# ATMEGA128.net
KiCad netlist of a schematic drawn in Altium Designer
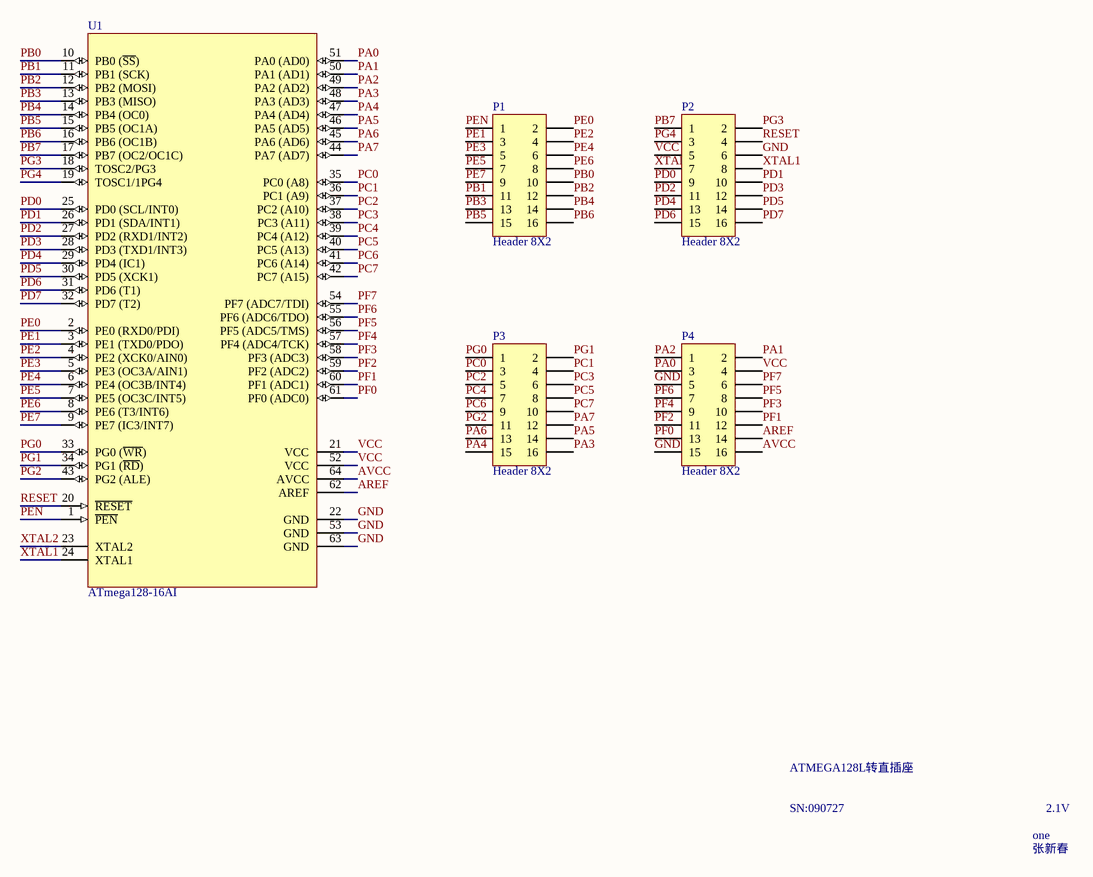
[diagram p0: ATMEGA128转换座.SchDoc]

(export (version "E")
  (design (tool "Eeschema 10.0.6"))
  (components
    (comp (ref "P1")
      (value "Header 8X2")
      (footprint "HDR2X8")
      (description "Header, 8-Pin, Dual row")
      (fields (field (name "PUBLISHER") "Altium Limited"))
      (libsource (lib "Miscellaneous Connectors") (part "Header 8X2"))
    )
    (comp (ref "P2")
      (value "Header 8X2")
      (footprint "HDR2X8")
      (description "Header, 8-Pin, Dual row")
      (fields (field (name "PUBLISHER") "Altium Limited"))
      (libsource (lib "Miscellaneous Connectors") (part "Header 8X2"))
    )
    (comp (ref "P3")
      (value "Header 8X2")
      (footprint "HDR2X8")
      (description "Header, 8-Pin, Dual row")
      (fields (field (name "PUBLISHER") "Altium Limited"))
      (libsource (lib "Miscellaneous Connectors") (part "Header 8X2"))
    )
    (comp (ref "P4")
      (value "Header 8X2")
      (footprint "HDR2X8")
      (description "Header, 8-Pin, Dual row")
      (fields (field (name "PUBLISHER") "Altium Limited"))
      (libsource (lib "Miscellaneous Connectors") (part "Header 8X2"))
    )
    (comp (ref "U1")
      (value "ATmega128-16AI")
      (footprint "64A")
      (description "8-Bit AVR Microcontroller with 128K Bytes of In-System Programmable Flash Memory")
      (fields (field (name "PUBLISHER") "Altium Limited"))
      (libsource (lib "Atmel Microcontroller 8-Bit AVR") (part "ATmega128-16AI"))
    )
  )
  (nets
    (net (code "1") (name "/AREF") (class "Default")
      (node (ref "P4") (pin "14") (pinfunction "14_14") (pintype "passive"))
      (node (ref "U1") (pin "62") (pinfunction "AREF_62") (pintype "passive"))
    )
    (net (code "2") (name "/AVCC") (class "Default")
      (node (ref "P4") (pin "16") (pinfunction "16_16") (pintype "passive"))
      (node (ref "U1") (pin "64") (pinfunction "AVCC_64") (pintype "power_in"))
    )
    (net (code "3") (name "/GND") (class "Default")
      (node (ref "P2") (pin "6") (pinfunction "6_6") (pintype "passive"))
      (node (ref "P4") (pin "15") (pinfunction "15_15") (pintype "passive"))
      (node (ref "P4") (pin "5") (pinfunction "5_5") (pintype "passive"))
      (node (ref "U1") (pin "22") (pinfunction "GND_22") (pintype "power_in"))
      (node (ref "U1") (pin "53") (pinfunction "GND_53") (pintype "power_in"))
      (node (ref "U1") (pin "63") (pinfunction "GND_63") (pintype "power_in"))
    )
    (net (code "4") (name "/PA0") (class "Default")
      (node (ref "P4") (pin "3") (pinfunction "3_3") (pintype "passive"))
      (node (ref "U1") (pin "51") (pinfunction "PA0_(AD0)_51") (pintype "bidirectional"))
    )
    (net (code "5") (name "/PA1") (class "Default")
      (node (ref "P4") (pin "2") (pinfunction "2_2") (pintype "passive"))
      (node (ref "U1") (pin "50") (pinfunction "PA1_(AD1)_50") (pintype "bidirectional"))
    )
    (net (code "6") (name "/PA2") (class "Default")
      (node (ref "P4") (pin "1") (pinfunction "1_1") (pintype "passive"))
      (node (ref "U1") (pin "49") (pinfunction "PA2_(AD2)_49") (pintype "bidirectional"))
    )
    (net (code "7") (name "/PA3") (class "Default")
      (node (ref "P3") (pin "16") (pinfunction "16_16") (pintype "passive"))
      (node (ref "U1") (pin "48") (pinfunction "PA3_(AD3)_48") (pintype "bidirectional"))
    )
    (net (code "8") (name "/PA4") (class "Default")
      (node (ref "P3") (pin "15") (pinfunction "15_15") (pintype "passive"))
      (node (ref "U1") (pin "47") (pinfunction "PA4_(AD4)_47") (pintype "bidirectional"))
    )
    (net (code "9") (name "/PA5") (class "Default")
      (node (ref "P3") (pin "14") (pinfunction "14_14") (pintype "passive"))
      (node (ref "U1") (pin "46") (pinfunction "PA5_(AD5)_46") (pintype "bidirectional"))
    )
    (net (code "10") (name "/PA6") (class "Default")
      (node (ref "P3") (pin "13") (pinfunction "13_13") (pintype "passive"))
      (node (ref "U1") (pin "45") (pinfunction "PA6_(AD6)_45") (pintype "bidirectional"))
    )
    (net (code "11") (name "/PA7") (class "Default")
      (node (ref "P3") (pin "12") (pinfunction "12_12") (pintype "passive"))
      (node (ref "U1") (pin "44") (pinfunction "PA7_(AD7)_44") (pintype "bidirectional"))
    )
    (net (code "12") (name "/PB0") (class "Default")
      (node (ref "P1") (pin "10") (pinfunction "10_10") (pintype "passive"))
      (node (ref "U1") (pin "10") (pinfunction "PB0_(~{SS})_10") (pintype "bidirectional"))
    )
    (net (code "13") (name "/PB1") (class "Default")
      (node (ref "P1") (pin "11") (pinfunction "11_11") (pintype "passive"))
      (node (ref "U1") (pin "11") (pinfunction "PB1_(SCK)_11") (pintype "bidirectional"))
    )
    (net (code "14") (name "/PB2") (class "Default")
      (node (ref "P1") (pin "12") (pinfunction "12_12") (pintype "passive"))
      (node (ref "U1") (pin "12") (pinfunction "PB2_(MOSI)_12") (pintype "bidirectional"))
    )
    (net (code "15") (name "/PB3") (class "Default")
      (node (ref "P1") (pin "13") (pinfunction "13_13") (pintype "passive"))
      (node (ref "U1") (pin "13") (pinfunction "PB3_(MISO)_13") (pintype "bidirectional"))
    )
    (net (code "16") (name "/PB4") (class "Default")
      (node (ref "P1") (pin "14") (pinfunction "14_14") (pintype "passive"))
      (node (ref "U1") (pin "14") (pinfunction "PB4_(OC0)_14") (pintype "bidirectional"))
    )
    (net (code "17") (name "/PB5") (class "Default")
      (node (ref "P1") (pin "15") (pinfunction "15_15") (pintype "passive"))
      (node (ref "U1") (pin "15") (pinfunction "PB5_(OC1A)_15") (pintype "bidirectional"))
    )
    (net (code "18") (name "/PB6") (class "Default")
      (node (ref "P1") (pin "16") (pinfunction "16_16") (pintype "passive"))
      (node (ref "U1") (pin "16") (pinfunction "PB6_(OC1B)_16") (pintype "bidirectional"))
    )
    (net (code "19") (name "/PB7") (class "Default")
      (node (ref "P2") (pin "1") (pinfunction "1_1") (pintype "passive"))
      (node (ref "U1") (pin "17") (pinfunction "PB7_(OC2/OC1C)_17") (pintype "bidirectional"))
    )
    (net (code "20") (name "/PC0") (class "Default")
      (node (ref "P3") (pin "3") (pinfunction "3_3") (pintype "passive"))
      (node (ref "U1") (pin "35") (pinfunction "PC0_(A8)_35") (pintype "bidirectional"))
    )
    (net (code "21") (name "/PC1") (class "Default")
      (node (ref "P3") (pin "4") (pinfunction "4_4") (pintype "passive"))
      (node (ref "U1") (pin "36") (pinfunction "PC1_(A9)_36") (pintype "bidirectional"))
    )
    (net (code "22") (name "/PC2") (class "Default")
      (node (ref "P3") (pin "5") (pinfunction "5_5") (pintype "passive"))
      (node (ref "U1") (pin "37") (pinfunction "PC2_(A10)_37") (pintype "bidirectional"))
    )
    (net (code "23") (name "/PC3") (class "Default")
      (node (ref "P3") (pin "6") (pinfunction "6_6") (pintype "passive"))
      (node (ref "U1") (pin "38") (pinfunction "PC3_(A11)_38") (pintype "bidirectional"))
    )
    (net (code "24") (name "/PC4") (class "Default")
      (node (ref "P3") (pin "7") (pinfunction "7_7") (pintype "passive"))
      (node (ref "U1") (pin "39") (pinfunction "PC4_(A12)_39") (pintype "bidirectional"))
    )
    (net (code "25") (name "/PC5") (class "Default")
      (node (ref "P3") (pin "8") (pinfunction "8_8") (pintype "passive"))
      (node (ref "U1") (pin "40") (pinfunction "PC5_(A13)_40") (pintype "bidirectional"))
    )
    (net (code "26") (name "/PC6") (class "Default")
      (node (ref "P3") (pin "9") (pinfunction "9_9") (pintype "passive"))
      (node (ref "U1") (pin "41") (pinfunction "PC6_(A14)_41") (pintype "bidirectional"))
    )
    (net (code "27") (name "/PC7") (class "Default")
      (node (ref "P3") (pin "10") (pinfunction "10_10") (pintype "passive"))
      (node (ref "U1") (pin "42") (pinfunction "PC7_(A15)_42") (pintype "bidirectional"))
    )
    (net (code "28") (name "/PD0") (class "Default")
      (node (ref "P2") (pin "9") (pinfunction "9_9") (pintype "passive"))
      (node (ref "U1") (pin "25") (pinfunction "PD0_(SCL/INT0)_25") (pintype "bidirectional"))
    )
    (net (code "29") (name "/PD1") (class "Default")
      (node (ref "P2") (pin "10") (pinfunction "10_10") (pintype "passive"))
      (node (ref "U1") (pin "26") (pinfunction "PD1_(SDA/INT1)_26") (pintype "bidirectional"))
    )
    (net (code "30") (name "/PD2") (class "Default")
      (node (ref "P2") (pin "11") (pinfunction "11_11") (pintype "passive"))
      (node (ref "U1") (pin "27") (pinfunction "PD2_(RXD1/INT2)_27") (pintype "bidirectional"))
    )
    (net (code "31") (name "/PD3") (class "Default")
      (node (ref "P2") (pin "12") (pinfunction "12_12") (pintype "passive"))
      (node (ref "U1") (pin "28") (pinfunction "PD3_(TXD1/INT3)_28") (pintype "bidirectional"))
    )
    (net (code "32") (name "/PD4") (class "Default")
      (node (ref "P2") (pin "13") (pinfunction "13_13") (pintype "passive"))
      (node (ref "U1") (pin "29") (pinfunction "PD4_(IC1)_29") (pintype "bidirectional"))
    )
    (net (code "33") (name "/PD5") (class "Default")
      (node (ref "P2") (pin "14") (pinfunction "14_14") (pintype "passive"))
      (node (ref "U1") (pin "30") (pinfunction "PD5_(XCK1)_30") (pintype "bidirectional"))
    )
    (net (code "34") (name "/PD6") (class "Default")
      (node (ref "P2") (pin "15") (pinfunction "15_15") (pintype "passive"))
      (node (ref "U1") (pin "31") (pinfunction "PD6_(T1)_31") (pintype "bidirectional"))
    )
    (net (code "35") (name "/PD7") (class "Default")
      (node (ref "P2") (pin "16") (pinfunction "16_16") (pintype "passive"))
      (node (ref "U1") (pin "32") (pinfunction "PD7_(T2)_32") (pintype "bidirectional"))
    )
    (net (code "36") (name "/PE0") (class "Default")
      (node (ref "P1") (pin "2") (pinfunction "2_2") (pintype "passive"))
      (node (ref "U1") (pin "2") (pinfunction "PE0_(RXD0/PDI)_2") (pintype "bidirectional"))
    )
    (net (code "37") (name "/PE1") (class "Default")
      (node (ref "P1") (pin "3") (pinfunction "3_3") (pintype "passive"))
      (node (ref "U1") (pin "3") (pinfunction "PE1_(TXD0/PDO)_3") (pintype "bidirectional"))
    )
    (net (code "38") (name "/PE2") (class "Default")
      (node (ref "P1") (pin "4") (pinfunction "4_4") (pintype "passive"))
      (node (ref "U1") (pin "4") (pinfunction "PE2_(XCK0/AIN0)_4") (pintype "bidirectional"))
    )
    (net (code "39") (name "/PE3") (class "Default")
      (node (ref "P1") (pin "5") (pinfunction "5_5") (pintype "passive"))
      (node (ref "U1") (pin "5") (pinfunction "PE3_(OC3A/AIN1)_5") (pintype "bidirectional"))
    )
    (net (code "40") (name "/PE4") (class "Default")
      (node (ref "P1") (pin "6") (pinfunction "6_6") (pintype "passive"))
      (node (ref "U1") (pin "6") (pinfunction "PE4_(OC3B/INT4)_6") (pintype "bidirectional"))
    )
    (net (code "41") (name "/PE5") (class "Default")
      (node (ref "P1") (pin "7") (pinfunction "7_7") (pintype "passive"))
      (node (ref "U1") (pin "7") (pinfunction "PE5_(OC3C/INT5)_7") (pintype "bidirectional"))
    )
    (net (code "42") (name "/PE6") (class "Default")
      (node (ref "P1") (pin "8") (pinfunction "8_8") (pintype "passive"))
      (node (ref "U1") (pin "8") (pinfunction "PE6_(T3/INT6)_8") (pintype "bidirectional"))
    )
    (net (code "43") (name "/PE7") (class "Default")
      (node (ref "P1") (pin "9") (pinfunction "9_9") (pintype "passive"))
      (node (ref "U1") (pin "9") (pinfunction "PE7_(IC3/INT7)_9") (pintype "bidirectional"))
    )
    (net (code "44") (name "/PEN") (class "Default")
      (node (ref "P1") (pin "1") (pinfunction "1_1") (pintype "passive"))
      (node (ref "U1") (pin "1") (pinfunction "~{PEN}_1") (pintype "input"))
    )
    (net (code "45") (name "/PF0") (class "Default")
      (node (ref "P4") (pin "13") (pinfunction "13_13") (pintype "passive"))
      (node (ref "U1") (pin "61") (pinfunction "PF0_(ADC0)_61") (pintype "bidirectional"))
    )
    (net (code "46") (name "/PF1") (class "Default")
      (node (ref "P4") (pin "12") (pinfunction "12_12") (pintype "passive"))
      (node (ref "U1") (pin "60") (pinfunction "PF1_(ADC1)_60") (pintype "bidirectional"))
    )
    (net (code "47") (name "/PF2") (class "Default")
      (node (ref "P4") (pin "11") (pinfunction "11_11") (pintype "passive"))
      (node (ref "U1") (pin "59") (pinfunction "PF2_(ADC2)_59") (pintype "bidirectional"))
    )
    (net (code "48") (name "/PF3") (class "Default")
      (node (ref "P4") (pin "10") (pinfunction "10_10") (pintype "passive"))
      (node (ref "U1") (pin "58") (pinfunction "PF3_(ADC3)_58") (pintype "bidirectional"))
    )
    (net (code "49") (name "/PF4") (class "Default")
      (node (ref "P4") (pin "9") (pinfunction "9_9") (pintype "passive"))
      (node (ref "U1") (pin "57") (pinfunction "PF4_(ADC4/TCK)_57") (pintype "bidirectional"))
    )
    (net (code "50") (name "/PF5") (class "Default")
      (node (ref "P4") (pin "8") (pinfunction "8_8") (pintype "passive"))
      (node (ref "U1") (pin "56") (pinfunction "PF5_(ADC5/TMS)_56") (pintype "bidirectional"))
    )
    (net (code "51") (name "/PF6") (class "Default")
      (node (ref "P4") (pin "7") (pinfunction "7_7") (pintype "passive"))
      (node (ref "U1") (pin "55") (pinfunction "PF6_(ADC6/TDO)_55") (pintype "bidirectional"))
    )
    (net (code "52") (name "/PF7") (class "Default")
      (node (ref "P4") (pin "6") (pinfunction "6_6") (pintype "passive"))
      (node (ref "U1") (pin "54") (pinfunction "PF7_(ADC7/TDI)_54") (pintype "bidirectional"))
    )
    (net (code "53") (name "/PG0") (class "Default")
      (node (ref "P3") (pin "1") (pinfunction "1_1") (pintype "passive"))
      (node (ref "U1") (pin "33") (pinfunction "PG0_(~{WR})_33") (pintype "bidirectional"))
    )
    (net (code "54") (name "/PG1") (class "Default")
      (node (ref "P3") (pin "2") (pinfunction "2_2") (pintype "passive"))
      (node (ref "U1") (pin "34") (pinfunction "PG1_(~{RD})_34") (pintype "bidirectional"))
    )
    (net (code "55") (name "/PG2") (class "Default")
      (node (ref "P3") (pin "11") (pinfunction "11_11") (pintype "passive"))
      (node (ref "U1") (pin "43") (pinfunction "PG2_(ALE)_43") (pintype "bidirectional"))
    )
    (net (code "56") (name "/PG3") (class "Default")
      (node (ref "P2") (pin "2") (pinfunction "2_2") (pintype "passive"))
      (node (ref "U1") (pin "18") (pinfunction "TOSC2/PG3_18") (pintype "bidirectional"))
    )
    (net (code "57") (name "/PG4") (class "Default")
      (node (ref "P2") (pin "3") (pinfunction "3_3") (pintype "passive"))
      (node (ref "U1") (pin "19") (pinfunction "TOSC1/1PG4_19") (pintype "bidirectional"))
    )
    (net (code "58") (name "/RESET") (class "Default")
      (node (ref "P2") (pin "4") (pinfunction "4_4") (pintype "passive"))
      (node (ref "U1") (pin "20") (pinfunction "~{RESET}_20") (pintype "input"))
    )
    (net (code "59") (name "/VCC") (class "Default")
      (node (ref "P2") (pin "5") (pinfunction "5_5") (pintype "passive"))
      (node (ref "P4") (pin "4") (pinfunction "4_4") (pintype "passive"))
      (node (ref "U1") (pin "21") (pinfunction "VCC_21") (pintype "power_in"))
      (node (ref "U1") (pin "52") (pinfunction "VCC_52") (pintype "power_in"))
    )
    (net (code "60") (name "/XTAL1") (class "Default")
      (node (ref "P2") (pin "8") (pinfunction "8_8") (pintype "passive"))
      (node (ref "U1") (pin "24") (pinfunction "XTAL1_24") (pintype "passive"))
    )
    (net (code "61") (name "/XTAL2") (class "Default")
      (node (ref "P2") (pin "7") (pinfunction "7_7") (pintype "passive"))
      (node (ref "U1") (pin "23") (pinfunction "XTAL2_23") (pintype "passive"))
    )
  )
)
